# dcdc.net
KiCad netlist of a schematic drawn in Altium Designer
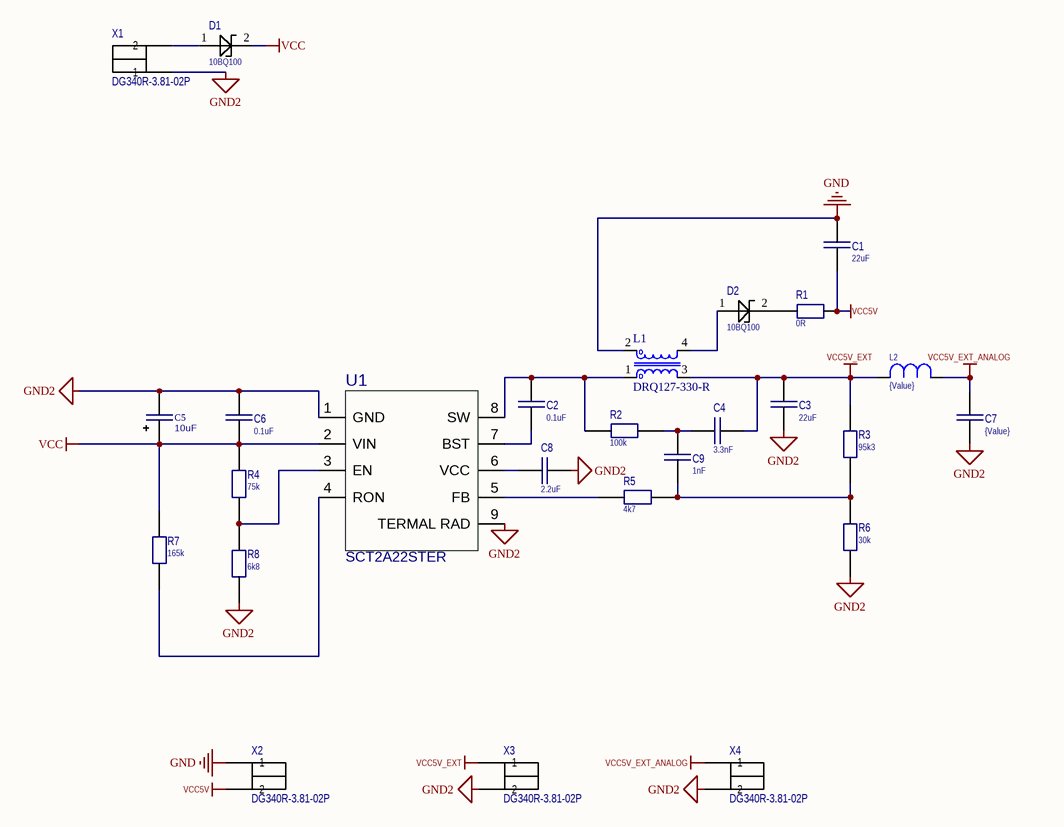
[diagram p0: dcdc.SchDoc]

(export (version "E")
  (design (tool "Eeschema 10.0.6"))
  (components
    (comp (ref "C1")
      (value "22uF")
      (footprint "C_0603")
      (description "Capacitor")
      (fields
        (field (name "PART NUMBER") "CC0603MRX5R6BB226")
        (field (name "ALTERNATIVE PART") "CC0603MRX6S5BB226")
      )
      (libsource (lib "capacitors") (part "C0603"))
    )
    (comp (ref "C2")
      (value "0.1uF")
      (footprint "C_0603")
      (description "Capacitor")
      (fields
        (field (name "PART NUMBER") "CC0603KRX7R9BB104")
        (field (name "ALTERNATIVE PART") "CC0603MRY5V9BB104")
      )
      (libsource (lib "capacitors") (part "C0603"))
    )
    (comp (ref "C3")
      (value "22uF")
      (footprint "C_0603")
      (description "Capacitor")
      (fields
        (field (name "PART NUMBER") "CC0603MRX5R6BB226")
        (field (name "ALTERNATIVE PART") "CC0603MRX6S5BB226")
      )
      (libsource (lib "capacitors") (part "C0603"))
    )
    (comp (ref "C4")
      (value "3.3nF")
      (footprint "C_0603")
      (description "Capacitor")
      (fields
        (field (name "PART NUMBER") "CC0603KRX7R9BB332")
        (field (name "ALTERNATIVE PART") "CC0603JRX7R9BB332")
      )
      (libsource (lib "capacitors") (part "C0603"))
    )
    (comp (ref "C5")
      (value "10uF")
      (footprint "CAP470X25V")
      (description "Capacitor")
      (fields (field (name "PART NUMBER") "SH160M0010B5S-1012"))
      (libsource (lib "capacitors") (part "C_10_12_5mm"))
    )
    (comp (ref "C6")
      (value "0.1uF")
      (footprint "C_1206")
      (description "Capacitor")
      (fields
        (field (name "PART NUMBER") "CC1206KKX7R0BB104")
        (field (name "ALTERNATIVE PART") "CC1206JKX7R0BB104")
      )
      (libsource (lib "capacitors") (part "C1206"))
    )
    (comp (ref "C7")
      (value "{Value}")
      (footprint "C_0603")
      (description "Capacitor")
      (libsource (lib "capacitors") (part "C0603"))
    )
    (comp (ref "C8")
      (value "2.2uF")
      (footprint "C_0603")
      (description "Capacitor")
      (fields (field (name "PART NUMBER") "CC0603KRX5R8BB225"))
      (libsource (lib "capacitors") (part "C0603"))
    )
    (comp (ref "C9")
      (value "1nF")
      (footprint "C_0603")
      (description "Capacitor")
      (fields
        (field (name "PART NUMBER") "CC0603KRX7R9BB102")
        (field (name "ALTERNATIVE PART") "CC0603KRX7R8BB102")
      )
      (libsource (lib "capacitors") (part "C0603"))
    )
    (comp (ref "D1")
      (value "10BQ100")
      (footprint "DO-214AA")
      (description "Diode")
      (fields (field (name "ALTERNATIVE PART") "VS-10BQ100"))
      (libsource (lib "diode") (part "D_DO-214AA"))
    )
    (comp (ref "D2")
      (value "10BQ100")
      (footprint "DO-214AA")
      (description "Diode")
      (fields (field (name "ALTERNATIVE PART") "VS-10BQ100"))
      (libsource (lib "diode") (part "D_DO-214AA"))
    )
    (comp (ref "L1")
      (value "DRQ127-330-R")
      (footprint "inductors_transformers:XFMR_DRQ127-150-R")
      (description "Inductor Power Shielded")
      (libsource (lib "inductors_transformers") (part "DRQ127-150-R"))
    )
    (comp (ref "L2")
      (value "{Value}")
      (footprint "CD54NP")
      (description "Inductor")
      (libsource (lib "inductors_transformers") (part "L_CD54NP"))
    )
    (comp (ref "R1")
      (value "0R")
      (footprint "R_0603")
      (description "Resistor")
      (fields
        (field (name "PART NUMBER") "RC0603JR-070RL")
        (field (name "ALTERNATIVE PART") "RC0603JR-100RL")
      )
      (libsource (lib "resistors") (part "R0603"))
    )
    (comp (ref "R2")
      (value "100k")
      (footprint "R_0603")
      (description "Resistor")
      (fields
        (field (name "PART NUMBER") "RC0603FR-07100KL")
        (field (name "ALTERNATIVE PART") "RC0603JR-07100KL")
      )
      (libsource (lib "resistors") (part "R0603"))
    )
    (comp (ref "R3")
      (value "95k3")
      (footprint "R_0603")
      (description "Resistor")
      (fields (field (name "PART NUMBER") "RC0603FR-0795K3L"))
      (libsource (lib "resistors") (part "R0603"))
    )
    (comp (ref "R4")
      (value "75k")
      (footprint "R_0603")
      (description "Resistor")
      (fields
        (field (name "PART NUMBER") "RC0603JR-0775KL")
        (field (name "ALTERNATIVE PART") "RC0603FR-0775KL")
      )
      (libsource (lib "resistors") (part "R0603"))
    )
    (comp (ref "R5")
      (value "4k7")
      (footprint "R_0603")
      (description "Resistor")
      (fields
        (field (name "PART NUMBER") "RC0603FR-074K7L")
        (field (name "ALTERNATIVE PART") "RC0603JR-074K7L")
      )
      (libsource (lib "resistors") (part "R0603"))
    )
    (comp (ref "R6")
      (value "30k")
      (footprint "R_0603")
      (description "Resistor")
      (fields
        (field (name "PART NUMBER") "RC0603FR-0730KL")
        (field (name "ALTERNATIVE PART") "RC0603JR-0730KL")
      )
      (libsource (lib "resistors") (part "R0603"))
    )
    (comp (ref "R7")
      (value "165k")
      (footprint "R_0603")
      (description "Resistor")
      (fields (field (name "PART NUMBER") "RC0603FR-07165KL"))
      (libsource (lib "resistors") (part "R0603"))
    )
    (comp (ref "R8")
      (value "6k8")
      (footprint "R_0603")
      (description "Resistor")
      (fields
        (field (name "PART NUMBER") "RC0603FR-076K8L")
        (field (name "ALTERNATIVE PART") "RC0603JR-076K8L")
      )
      (libsource (lib "resistors") (part "R0603"))
    )
    (comp (ref "U1")
      (value "SCT2A22STER")
      (footprint "ESOP-8")
      (description "Buck dc/dc")
      (libsource (lib "dcdc_ldo_ref") (part "SCT2A22STER"))
    )
    (comp (ref "X1")
      (value "DG340R-3.81-02P")
      (footprint "340-021-12")
      (description "Connectors")
      (fields
        (field (name "TYPE") "DG340R-3.81-02P")
        (field (name "ALTERNATIVE PART") "KLS2-340-3.81-02P-2S")
      )
      (libsource (lib "connectors_socets") (part "DG340R-3.81-02P"))
    )
    (comp (ref "X2")
      (value "DG340R-3.81-02P")
      (footprint "340-021-12")
      (description "Connectors")
      (fields
        (field (name "TYPE") "DG340R-3.81-02P")
        (field (name "ALTERNATIVE PART") "KLS2-340-3.81-02P-2S")
      )
      (libsource (lib "connectors_socets") (part "DG340R-3.81-02P"))
    )
    (comp (ref "X3")
      (value "DG340R-3.81-02P")
      (footprint "340-021-12")
      (description "Connectors")
      (fields
        (field (name "TYPE") "DG340R-3.81-02P")
        (field (name "ALTERNATIVE PART") "KLS2-340-3.81-02P-2S")
      )
      (libsource (lib "connectors_socets") (part "DG340R-3.81-02P"))
    )
    (comp (ref "X4")
      (value "DG340R-3.81-02P")
      (footprint "340-021-12")
      (description "Connectors")
      (fields
        (field (name "TYPE") "DG340R-3.81-02P")
        (field (name "ALTERNATIVE PART") "KLS2-340-3.81-02P-2S")
      )
      (libsource (lib "connectors_socets") (part "DG340R-3.81-02P"))
    )
  )
  (nets
    (net (code "1") (name "GND") (class "Default")
      (node (ref "C1") (pin "2") (pinfunction "2_2") (pintype "passive"))
      (node (ref "L1") (pin "2") (pinfunction "2_2") (pintype "passive"))
      (node (ref "X2") (pin "1") (pinfunction "1_1") (pintype "passive"))
    )
    (net (code "2") (name "GND2") (class "Default")
      (node (ref "C3") (pin "1") (pinfunction "1_1") (pintype "passive"))
      (node (ref "C5") (pin "1") (pinfunction "1_1") (pintype "passive"))
      (node (ref "C6") (pin "2") (pinfunction "2_2") (pintype "passive"))
      (node (ref "C7") (pin "1") (pinfunction "1_1") (pintype "passive"))
      (node (ref "C8") (pin "1") (pinfunction "1_1") (pintype "passive"))
      (node (ref "R6") (pin "1") (pinfunction "1_1") (pintype "passive"))
      (node (ref "R8") (pin "1") (pinfunction "1_1") (pintype "passive"))
      (node (ref "U1") (pin "1") (pinfunction "GND_1") (pintype "passive"))
      (node (ref "U1") (pin "9") (pinfunction "TERMAL_RAD_9") (pintype "passive"))
      (node (ref "X1") (pin "1") (pinfunction "1_1") (pintype "passive"))
      (node (ref "X3") (pin "2") (pinfunction "2_2") (pintype "passive"))
      (node (ref "X4") (pin "2") (pinfunction "2_2") (pintype "passive"))
    )
    (net (code "3") (name "Net-(C4-Pad1)") (class "Default")
      (node (ref "C4") (pin "1") (pinfunction "1_1") (pintype "passive"))
      (node (ref "C9") (pin "1") (pinfunction "1_1") (pintype "passive"))
      (node (ref "R2") (pin "1") (pinfunction "1_1") (pintype "passive"))
    )
    (net (code "4") (name "Net-(C9-Pad2)") (class "Default")
      (node (ref "C9") (pin "2") (pinfunction "2_2") (pintype "passive"))
      (node (ref "R3") (pin "1") (pinfunction "1_1") (pintype "passive"))
      (node (ref "R5") (pin "2") (pinfunction "2_2") (pintype "passive"))
      (node (ref "R6") (pin "2") (pinfunction "2_2") (pintype "passive"))
    )
    (net (code "5") (name "Net-(D1-A)") (class "Default")
      (node (ref "D1") (pin "1") (pinfunction "A_1") (pintype "passive"))
      (node (ref "X1") (pin "2") (pinfunction "2_2") (pintype "passive"))
    )
    (net (code "6") (name "Net-(D2-A)") (class "Default")
      (node (ref "D2") (pin "1") (pinfunction "A_1") (pintype "passive"))
      (node (ref "L1") (pin "4") (pinfunction "4_4") (pintype "passive"))
    )
    (net (code "7") (name "Net-(D2-K)") (class "Default")
      (node (ref "D2") (pin "2") (pinfunction "K_2") (pintype "passive"))
      (node (ref "R1") (pin "2") (pinfunction "2_2") (pintype "passive"))
    )
    (net (code "8") (name "Net-(U1-BST)") (class "Default")
      (node (ref "C2") (pin "1") (pinfunction "1_1") (pintype "passive"))
      (node (ref "U1") (pin "7") (pinfunction "BST_7") (pintype "passive"))
    )
    (net (code "9") (name "Net-(U1-EN)") (class "Default")
      (node (ref "R4") (pin "1") (pinfunction "1_1") (pintype "passive"))
      (node (ref "R8") (pin "2") (pinfunction "2_2") (pintype "passive"))
      (node (ref "U1") (pin "3") (pinfunction "EN_3") (pintype "passive"))
    )
    (net (code "10") (name "Net-(U1-FB)") (class "Default")
      (node (ref "R5") (pin "1") (pinfunction "1_1") (pintype "passive"))
      (node (ref "U1") (pin "5") (pinfunction "FB_5") (pintype "passive"))
    )
    (net (code "11") (name "Net-(U1-RON)") (class "Default")
      (node (ref "R7") (pin "1") (pinfunction "1_1") (pintype "passive"))
      (node (ref "U1") (pin "4") (pinfunction "RON_4") (pintype "passive"))
    )
    (net (code "12") (name "Net-(U1-SW)") (class "Default")
      (node (ref "C2") (pin "2") (pinfunction "2_2") (pintype "passive"))
      (node (ref "L1") (pin "1") (pinfunction "1_1") (pintype "passive"))
      (node (ref "R2") (pin "2") (pinfunction "2_2") (pintype "passive"))
      (node (ref "U1") (pin "8") (pinfunction "SW_8") (pintype "passive"))
    )
    (net (code "13") (name "Net-(U1-VCC)") (class "Default")
      (node (ref "C8") (pin "2") (pinfunction "2_2") (pintype "passive"))
      (node (ref "U1") (pin "6") (pinfunction "VCC_6") (pintype "passive"))
    )
    (net (code "14") (name "VCC") (class "Default")
      (node (ref "C5") (pin "2") (pinfunction "2_2") (pintype "passive"))
      (node (ref "C6") (pin "1") (pinfunction "1_1") (pintype "passive"))
      (node (ref "D1") (pin "2") (pinfunction "K_2") (pintype "passive"))
      (node (ref "R4") (pin "2") (pinfunction "2_2") (pintype "passive"))
      (node (ref "R7") (pin "2") (pinfunction "2_2") (pintype "passive"))
      (node (ref "U1") (pin "2") (pinfunction "VIN_2") (pintype "passive"))
    )
    (net (code "15") (name "VCC5V") (class "Default")
      (node (ref "C1") (pin "1") (pinfunction "1_1") (pintype "passive"))
      (node (ref "R1") (pin "1") (pinfunction "1_1") (pintype "passive"))
      (node (ref "X2") (pin "2") (pinfunction "2_2") (pintype "passive"))
    )
    (net (code "16") (name "VCC5V_EXT") (class "Default")
      (node (ref "C3") (pin "2") (pinfunction "2_2") (pintype "passive"))
      (node (ref "C4") (pin "2") (pinfunction "2_2") (pintype "passive"))
      (node (ref "L1") (pin "3") (pinfunction "3_3") (pintype "passive"))
      (node (ref "L2") (pin "2") (pintype "passive"))
      (node (ref "R3") (pin "2") (pinfunction "2_2") (pintype "passive"))
      (node (ref "X3") (pin "1") (pinfunction "1_1") (pintype "passive"))
    )
    (net (code "17") (name "VCC5V_EXT_ANALOG") (class "Default")
      (node (ref "C7") (pin "2") (pinfunction "2_2") (pintype "passive"))
      (node (ref "L2") (pin "1") (pintype "passive"))
      (node (ref "X4") (pin "1") (pinfunction "1_1") (pintype "passive"))
    )
  )
)
